# IOBRMEGA.net
KiCad netlist of a schematic drawn in EAGLE
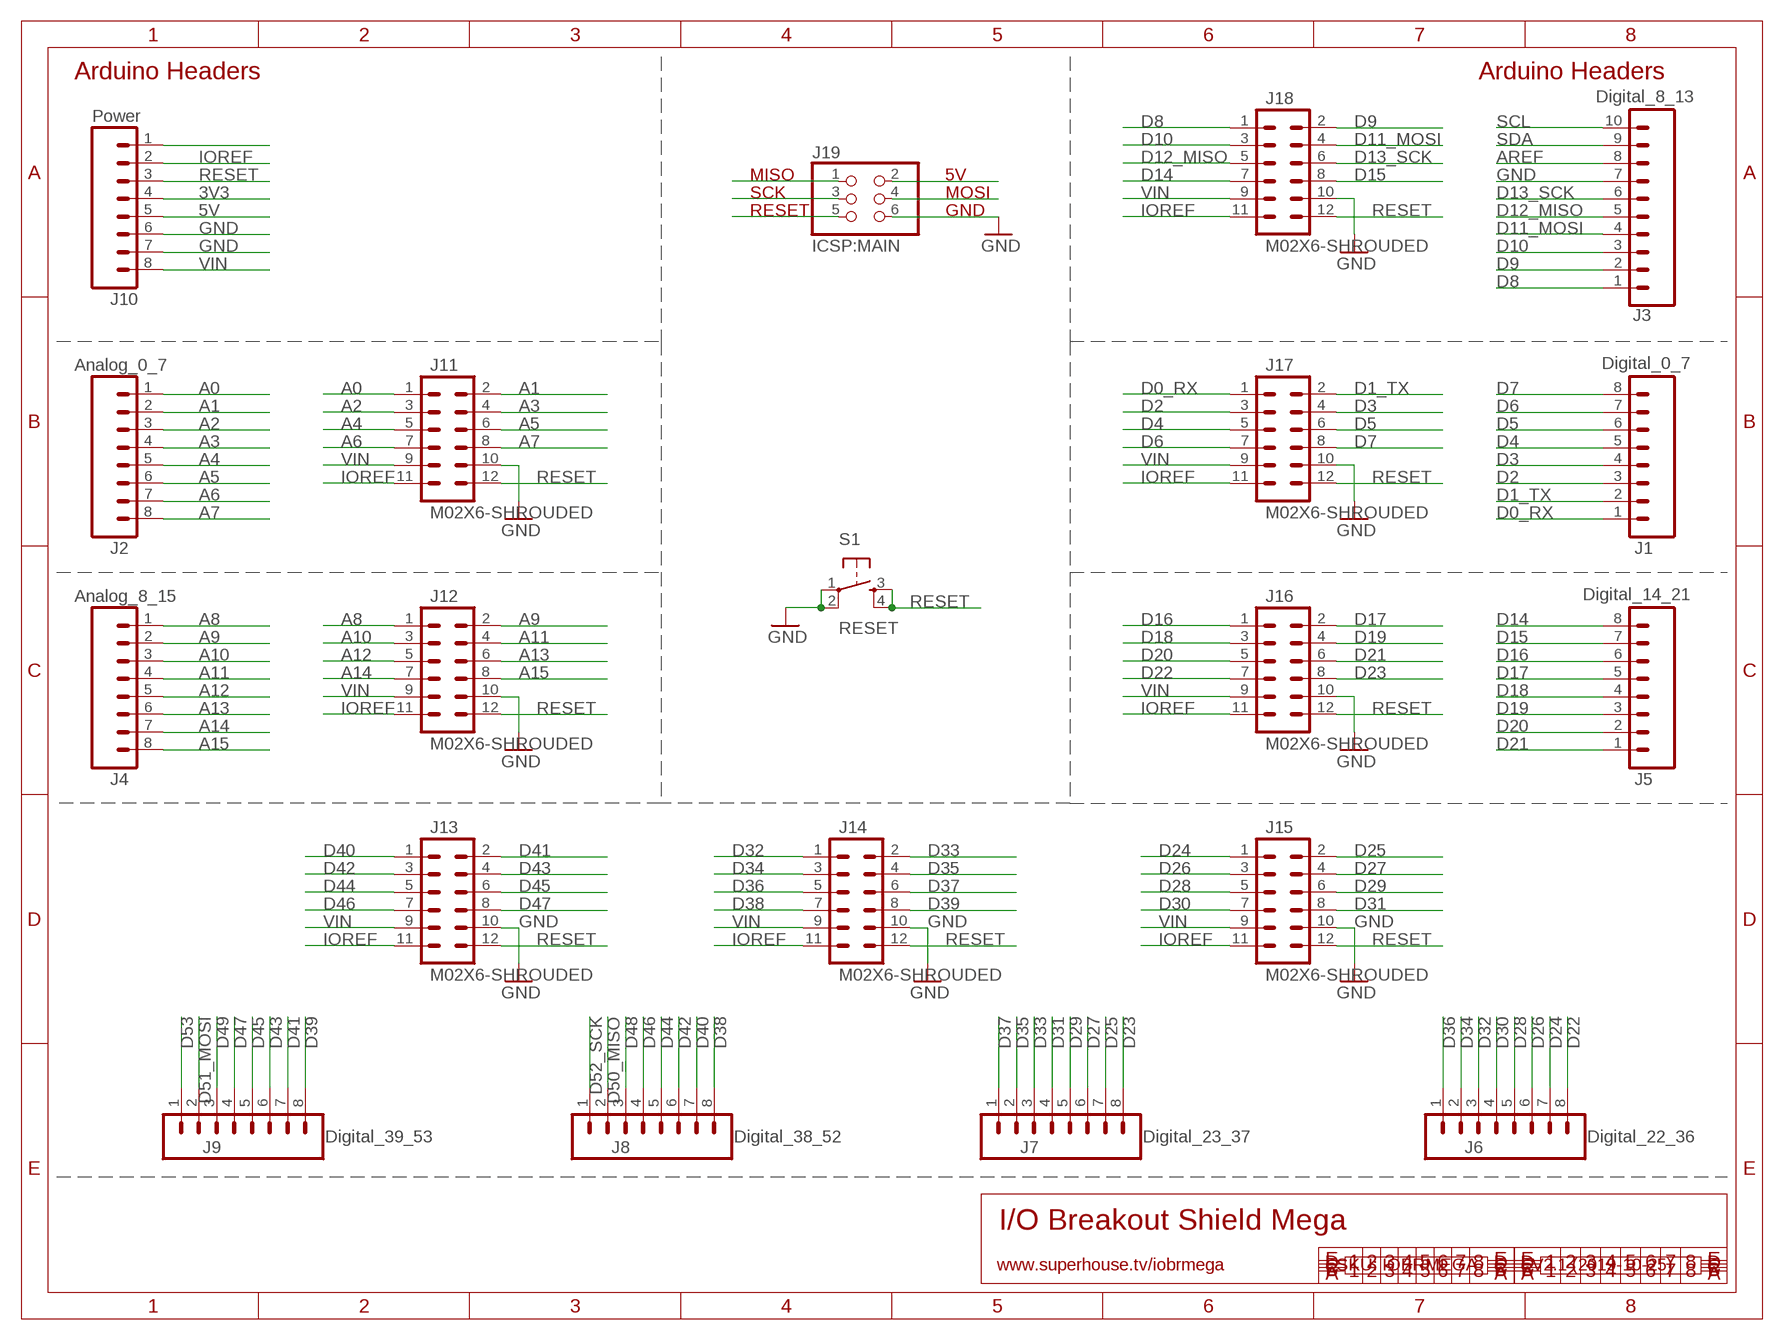
[diagram p0: schematic, sheet 1]

(export (version "E")
  (design (tool "Eeschema 10.0.6"))
  (components
    (comp (ref "J1")
      (value "Digital_0_7")
      (footprint "eagle-import:1X08-P-BELOW")
      (libsource (lib "eagle-import") (part "M08-PIN-BELOW"))
    )
    (comp (ref "J2")
      (value "Analog_0_7")
      (footprint "eagle-import:1X08-P-BELOW")
      (libsource (lib "eagle-import") (part "M08-PIN-BELOW"))
    )
    (comp (ref "J3")
      (value "Digital_8_13")
      (footprint "eagle-import:1X10-P-BELOW")
      (libsource (lib "eagle-import") (part "M10-PIN-BELOW"))
    )
    (comp (ref "J4")
      (value "Analog_8_15")
      (footprint "eagle-import:1X08-P-BELOW")
      (libsource (lib "eagle-import") (part "M08-PIN-BELOW"))
    )
    (comp (ref "J5")
      (value "Digital_14_21")
      (footprint "eagle-import:1X08-P-BELOW")
      (libsource (lib "eagle-import") (part "M08-PIN-BELOW"))
    )
    (comp (ref "J6")
      (value "Digital_22_36")
      (footprint "eagle-import:1X08-P-BELOW")
      (libsource (lib "eagle-import") (part "M08-PIN-BELOW"))
    )
    (comp (ref "J7")
      (value "Digital_23_37")
      (footprint "eagle-import:1X08-P-BELOW")
      (libsource (lib "eagle-import") (part "M08-PIN-BELOW"))
    )
    (comp (ref "J8")
      (value "Digital_38_52")
      (footprint "eagle-import:1X08-P-BELOW")
      (libsource (lib "eagle-import") (part "M08-PIN-BELOW"))
    )
    (comp (ref "J9")
      (value "Digital_39_53")
      (footprint "eagle-import:1X08-P-BELOW")
      (libsource (lib "eagle-import") (part "M08-PIN-BELOW"))
    )
    (comp (ref "J10")
      (value "Power")
      (footprint "eagle-import:1X08-P-BELOW")
      (libsource (lib "eagle-import") (part "M08-PIN-BELOW"))
    )
    (comp (ref "J11")
      (value "M02X6-SHROUDED")
      (footprint "eagle-import:2X06-SHROUDED")
      (libsource (lib "eagle-import") (part "M02X6-SHROUDED"))
    )
    (comp (ref "J12")
      (value "M02X6-SHROUDED")
      (footprint "eagle-import:2X06-SHROUDED")
      (libsource (lib "eagle-import") (part "M02X6-SHROUDED"))
    )
    (comp (ref "J13")
      (value "M02X6-SHROUDED")
      (footprint "eagle-import:2X06-SHROUDED")
      (libsource (lib "eagle-import") (part "M02X6-SHROUDED"))
    )
    (comp (ref "J14")
      (value "M02X6-SHROUDED")
      (footprint "eagle-import:2X06-SHROUDED")
      (libsource (lib "eagle-import") (part "M02X6-SHROUDED"))
    )
    (comp (ref "J15")
      (value "M02X6-SHROUDED")
      (footprint "eagle-import:2X06-SHROUDED")
      (libsource (lib "eagle-import") (part "M02X6-SHROUDED"))
    )
    (comp (ref "J16")
      (value "M02X6-SHROUDED")
      (footprint "eagle-import:2X06-SHROUDED")
      (libsource (lib "eagle-import") (part "M02X6-SHROUDED"))
    )
    (comp (ref "J17")
      (value "M02X6-SHROUDED")
      (footprint "eagle-import:2X06-SHROUDED")
      (libsource (lib "eagle-import") (part "M02X6-SHROUDED"))
    )
    (comp (ref "J18")
      (value "M02X6-SHROUDED")
      (footprint "eagle-import:2X06-SHROUDED")
      (libsource (lib "eagle-import") (part "M02X6-SHROUDED"))
    )
    (comp (ref "J19")
      (value "ICSP:MAIN")
      (footprint "eagle-import:2X03")
      (libsource (lib "eagle-import") (part "PINHD-2X3"))
    )
    (comp (ref "S1")
      (value "RESET")
      (footprint "eagle-import:TACTILE-PTH-6MM")
      (libsource (lib "eagle-import") (part "TAC_SWITCH-PTH-6"))
    )
  )
  (nets
    (net (code "1") (name "/3V3") (class "Default")
      (node (ref "J10") (pin "4") (pinfunction "4_4") (pintype "passive"))
    )
    (net (code "2") (name "/5V") (class "Default")
      (node (ref "J10") (pin "5") (pinfunction "5_5") (pintype "passive"))
    )
    (net (code "3") (name "/A0") (class "Default")
      (node (ref "J11") (pin "1") (pinfunction "1_1") (pintype "passive"))
      (node (ref "J2") (pin "1") (pinfunction "1_1") (pintype "passive"))
    )
    (net (code "4") (name "/A1") (class "Default")
      (node (ref "J11") (pin "2") (pinfunction "2_2") (pintype "passive"))
      (node (ref "J2") (pin "2") (pinfunction "2_2") (pintype "passive"))
    )
    (net (code "5") (name "/A2") (class "Default")
      (node (ref "J11") (pin "3") (pinfunction "3_3") (pintype "passive"))
      (node (ref "J2") (pin "3") (pinfunction "3_3") (pintype "passive"))
    )
    (net (code "6") (name "/A3") (class "Default")
      (node (ref "J11") (pin "4") (pinfunction "4_4") (pintype "passive"))
      (node (ref "J2") (pin "4") (pinfunction "4_4") (pintype "passive"))
    )
    (net (code "7") (name "/A4") (class "Default")
      (node (ref "J11") (pin "5") (pinfunction "5_5") (pintype "passive"))
      (node (ref "J2") (pin "5") (pinfunction "5_5") (pintype "passive"))
    )
    (net (code "8") (name "/A5") (class "Default")
      (node (ref "J11") (pin "6") (pinfunction "6_6") (pintype "passive"))
      (node (ref "J2") (pin "6") (pinfunction "6_6") (pintype "passive"))
    )
    (net (code "9") (name "/A6") (class "Default")
      (node (ref "J11") (pin "7") (pinfunction "7_7") (pintype "passive"))
      (node (ref "J2") (pin "7") (pinfunction "7_7") (pintype "passive"))
    )
    (net (code "10") (name "/A7") (class "Default")
      (node (ref "J11") (pin "8") (pinfunction "8_8") (pintype "passive"))
      (node (ref "J2") (pin "8") (pinfunction "8_8") (pintype "passive"))
    )
    (net (code "11") (name "/A8") (class "Default")
      (node (ref "J12") (pin "1") (pinfunction "1_1") (pintype "passive"))
      (node (ref "J4") (pin "1") (pinfunction "1_1") (pintype "passive"))
    )
    (net (code "12") (name "/A9") (class "Default")
      (node (ref "J12") (pin "2") (pinfunction "2_2") (pintype "passive"))
      (node (ref "J4") (pin "2") (pinfunction "2_2") (pintype "passive"))
    )
    (net (code "13") (name "/A10") (class "Default")
      (node (ref "J12") (pin "3") (pinfunction "3_3") (pintype "passive"))
      (node (ref "J4") (pin "3") (pinfunction "3_3") (pintype "passive"))
    )
    (net (code "14") (name "/A11") (class "Default")
      (node (ref "J12") (pin "4") (pinfunction "4_4") (pintype "passive"))
      (node (ref "J4") (pin "4") (pinfunction "4_4") (pintype "passive"))
    )
    (net (code "15") (name "/A12") (class "Default")
      (node (ref "J12") (pin "5") (pinfunction "5_5") (pintype "passive"))
      (node (ref "J4") (pin "5") (pinfunction "5_5") (pintype "passive"))
    )
    (net (code "16") (name "/A13") (class "Default")
      (node (ref "J12") (pin "6") (pinfunction "6_6") (pintype "passive"))
      (node (ref "J4") (pin "6") (pinfunction "6_6") (pintype "passive"))
    )
    (net (code "17") (name "/A14") (class "Default")
      (node (ref "J12") (pin "7") (pinfunction "7_7") (pintype "passive"))
      (node (ref "J4") (pin "7") (pinfunction "7_7") (pintype "passive"))
    )
    (net (code "18") (name "/A15") (class "Default")
      (node (ref "J12") (pin "8") (pinfunction "8_8") (pintype "passive"))
      (node (ref "J4") (pin "8") (pinfunction "8_8") (pintype "passive"))
    )
    (net (code "19") (name "/AREF") (class "Default")
      (node (ref "J3") (pin "8") (pinfunction "8_8") (pintype "passive"))
    )
    (net (code "20") (name "/D0_RX") (class "Default")
      (node (ref "J1") (pin "1") (pinfunction "1_1") (pintype "passive"))
      (node (ref "J17") (pin "1") (pinfunction "1_1") (pintype "passive"))
    )
    (net (code "21") (name "/D1_TX") (class "Default")
      (node (ref "J1") (pin "2") (pinfunction "2_2") (pintype "passive"))
      (node (ref "J17") (pin "2") (pinfunction "2_2") (pintype "passive"))
    )
    (net (code "22") (name "/D2") (class "Default")
      (node (ref "J1") (pin "3") (pinfunction "3_3") (pintype "passive"))
      (node (ref "J17") (pin "3") (pinfunction "3_3") (pintype "passive"))
    )
    (net (code "23") (name "/D3") (class "Default")
      (node (ref "J1") (pin "4") (pinfunction "4_4") (pintype "passive"))
      (node (ref "J17") (pin "4") (pinfunction "4_4") (pintype "passive"))
    )
    (net (code "24") (name "/D4") (class "Default")
      (node (ref "J1") (pin "5") (pinfunction "5_5") (pintype "passive"))
      (node (ref "J17") (pin "5") (pinfunction "5_5") (pintype "passive"))
    )
    (net (code "25") (name "/D5") (class "Default")
      (node (ref "J1") (pin "6") (pinfunction "6_6") (pintype "passive"))
      (node (ref "J17") (pin "6") (pinfunction "6_6") (pintype "passive"))
    )
    (net (code "26") (name "/D6") (class "Default")
      (node (ref "J1") (pin "7") (pinfunction "7_7") (pintype "passive"))
      (node (ref "J17") (pin "7") (pinfunction "7_7") (pintype "passive"))
    )
    (net (code "27") (name "/D7") (class "Default")
      (node (ref "J1") (pin "8") (pinfunction "8_8") (pintype "passive"))
      (node (ref "J17") (pin "8") (pinfunction "8_8") (pintype "passive"))
    )
    (net (code "28") (name "/D8") (class "Default")
      (node (ref "J18") (pin "1") (pinfunction "1_1") (pintype "passive"))
      (node (ref "J3") (pin "1") (pinfunction "1_1") (pintype "passive"))
    )
    (net (code "29") (name "/D9") (class "Default")
      (node (ref "J18") (pin "2") (pinfunction "2_2") (pintype "passive"))
      (node (ref "J3") (pin "2") (pinfunction "2_2") (pintype "passive"))
    )
    (net (code "30") (name "/D10") (class "Default")
      (node (ref "J18") (pin "3") (pinfunction "3_3") (pintype "passive"))
      (node (ref "J3") (pin "3") (pinfunction "3_3") (pintype "passive"))
    )
    (net (code "31") (name "/D11_MOSI") (class "Default")
      (node (ref "J18") (pin "4") (pinfunction "4_4") (pintype "passive"))
      (node (ref "J3") (pin "4") (pinfunction "4_4") (pintype "passive"))
    )
    (net (code "32") (name "/D12_MISO") (class "Default")
      (node (ref "J18") (pin "5") (pinfunction "5_5") (pintype "passive"))
      (node (ref "J3") (pin "5") (pinfunction "5_5") (pintype "passive"))
    )
    (net (code "33") (name "/D13_SCK") (class "Default")
      (node (ref "J18") (pin "6") (pinfunction "6_6") (pintype "passive"))
      (node (ref "J3") (pin "6") (pinfunction "6_6") (pintype "passive"))
    )
    (net (code "34") (name "/D14") (class "Default")
      (node (ref "J18") (pin "7") (pinfunction "7_7") (pintype "passive"))
      (node (ref "J5") (pin "8") (pinfunction "8_8") (pintype "passive"))
    )
    (net (code "35") (name "/D15") (class "Default")
      (node (ref "J18") (pin "8") (pinfunction "8_8") (pintype "passive"))
      (node (ref "J5") (pin "7") (pinfunction "7_7") (pintype "passive"))
    )
    (net (code "36") (name "/D16") (class "Default")
      (node (ref "J16") (pin "1") (pinfunction "1_1") (pintype "passive"))
      (node (ref "J5") (pin "6") (pinfunction "6_6") (pintype "passive"))
    )
    (net (code "37") (name "/D17") (class "Default")
      (node (ref "J16") (pin "2") (pinfunction "2_2") (pintype "passive"))
      (node (ref "J5") (pin "5") (pinfunction "5_5") (pintype "passive"))
    )
    (net (code "38") (name "/D18") (class "Default")
      (node (ref "J16") (pin "3") (pinfunction "3_3") (pintype "passive"))
      (node (ref "J5") (pin "4") (pinfunction "4_4") (pintype "passive"))
    )
    (net (code "39") (name "/D19") (class "Default")
      (node (ref "J16") (pin "4") (pinfunction "4_4") (pintype "passive"))
      (node (ref "J5") (pin "3") (pinfunction "3_3") (pintype "passive"))
    )
    (net (code "40") (name "/D20") (class "Default")
      (node (ref "J16") (pin "5") (pinfunction "5_5") (pintype "passive"))
      (node (ref "J5") (pin "2") (pinfunction "2_2") (pintype "passive"))
    )
    (net (code "41") (name "/D21") (class "Default")
      (node (ref "J16") (pin "6") (pinfunction "6_6") (pintype "passive"))
      (node (ref "J5") (pin "1") (pinfunction "1_1") (pintype "passive"))
    )
    (net (code "42") (name "/D22") (class "Default")
      (node (ref "J16") (pin "7") (pinfunction "7_7") (pintype "passive"))
      (node (ref "J6") (pin "8") (pinfunction "8_8") (pintype "passive"))
    )
    (net (code "43") (name "/D23") (class "Default")
      (node (ref "J16") (pin "8") (pinfunction "8_8") (pintype "passive"))
      (node (ref "J7") (pin "8") (pinfunction "8_8") (pintype "passive"))
    )
    (net (code "44") (name "/D24") (class "Default")
      (node (ref "J15") (pin "1") (pinfunction "1_1") (pintype "passive"))
      (node (ref "J6") (pin "7") (pinfunction "7_7") (pintype "passive"))
    )
    (net (code "45") (name "/D25") (class "Default")
      (node (ref "J15") (pin "2") (pinfunction "2_2") (pintype "passive"))
      (node (ref "J7") (pin "7") (pinfunction "7_7") (pintype "passive"))
    )
    (net (code "46") (name "/D26") (class "Default")
      (node (ref "J15") (pin "3") (pinfunction "3_3") (pintype "passive"))
      (node (ref "J6") (pin "6") (pinfunction "6_6") (pintype "passive"))
    )
    (net (code "47") (name "/D27") (class "Default")
      (node (ref "J15") (pin "4") (pinfunction "4_4") (pintype "passive"))
      (node (ref "J7") (pin "6") (pinfunction "6_6") (pintype "passive"))
    )
    (net (code "48") (name "/D28") (class "Default")
      (node (ref "J15") (pin "5") (pinfunction "5_5") (pintype "passive"))
      (node (ref "J6") (pin "5") (pinfunction "5_5") (pintype "passive"))
    )
    (net (code "49") (name "/D29") (class "Default")
      (node (ref "J15") (pin "6") (pinfunction "6_6") (pintype "passive"))
      (node (ref "J7") (pin "5") (pinfunction "5_5") (pintype "passive"))
    )
    (net (code "50") (name "/D30") (class "Default")
      (node (ref "J15") (pin "7") (pinfunction "7_7") (pintype "passive"))
      (node (ref "J6") (pin "4") (pinfunction "4_4") (pintype "passive"))
    )
    (net (code "51") (name "/D31") (class "Default")
      (node (ref "J15") (pin "8") (pinfunction "8_8") (pintype "passive"))
      (node (ref "J7") (pin "4") (pinfunction "4_4") (pintype "passive"))
    )
    (net (code "52") (name "/D32") (class "Default")
      (node (ref "J14") (pin "1") (pinfunction "1_1") (pintype "passive"))
      (node (ref "J6") (pin "3") (pinfunction "3_3") (pintype "passive"))
    )
    (net (code "53") (name "/D33") (class "Default")
      (node (ref "J14") (pin "2") (pinfunction "2_2") (pintype "passive"))
      (node (ref "J7") (pin "3") (pinfunction "3_3") (pintype "passive"))
    )
    (net (code "54") (name "/D34") (class "Default")
      (node (ref "J14") (pin "3") (pinfunction "3_3") (pintype "passive"))
      (node (ref "J6") (pin "2") (pinfunction "2_2") (pintype "passive"))
    )
    (net (code "55") (name "/D35") (class "Default")
      (node (ref "J14") (pin "4") (pinfunction "4_4") (pintype "passive"))
      (node (ref "J7") (pin "2") (pinfunction "2_2") (pintype "passive"))
    )
    (net (code "56") (name "/D36") (class "Default")
      (node (ref "J14") (pin "5") (pinfunction "5_5") (pintype "passive"))
      (node (ref "J6") (pin "1") (pinfunction "1_1") (pintype "passive"))
    )
    (net (code "57") (name "/D37") (class "Default")
      (node (ref "J14") (pin "6") (pinfunction "6_6") (pintype "passive"))
      (node (ref "J7") (pin "1") (pinfunction "1_1") (pintype "passive"))
    )
    (net (code "58") (name "/D38") (class "Default")
      (node (ref "J14") (pin "7") (pinfunction "7_7") (pintype "passive"))
      (node (ref "J8") (pin "8") (pinfunction "8_8") (pintype "passive"))
    )
    (net (code "59") (name "/D39") (class "Default")
      (node (ref "J14") (pin "8") (pinfunction "8_8") (pintype "passive"))
      (node (ref "J9") (pin "8") (pinfunction "8_8") (pintype "passive"))
    )
    (net (code "60") (name "/D40") (class "Default")
      (node (ref "J13") (pin "1") (pinfunction "1_1") (pintype "passive"))
      (node (ref "J8") (pin "7") (pinfunction "7_7") (pintype "passive"))
    )
    (net (code "61") (name "/D41") (class "Default")
      (node (ref "J13") (pin "2") (pinfunction "2_2") (pintype "passive"))
      (node (ref "J9") (pin "7") (pinfunction "7_7") (pintype "passive"))
    )
    (net (code "62") (name "/D42") (class "Default")
      (node (ref "J13") (pin "3") (pinfunction "3_3") (pintype "passive"))
      (node (ref "J8") (pin "6") (pinfunction "6_6") (pintype "passive"))
    )
    (net (code "63") (name "/D43") (class "Default")
      (node (ref "J13") (pin "4") (pinfunction "4_4") (pintype "passive"))
      (node (ref "J9") (pin "6") (pinfunction "6_6") (pintype "passive"))
    )
    (net (code "64") (name "/D44") (class "Default")
      (node (ref "J13") (pin "5") (pinfunction "5_5") (pintype "passive"))
      (node (ref "J8") (pin "5") (pinfunction "5_5") (pintype "passive"))
    )
    (net (code "65") (name "/D45") (class "Default")
      (node (ref "J13") (pin "6") (pinfunction "6_6") (pintype "passive"))
      (node (ref "J9") (pin "5") (pinfunction "5_5") (pintype "passive"))
    )
    (net (code "66") (name "/D46") (class "Default")
      (node (ref "J13") (pin "7") (pinfunction "7_7") (pintype "passive"))
      (node (ref "J8") (pin "4") (pinfunction "4_4") (pintype "passive"))
    )
    (net (code "67") (name "/D47") (class "Default")
      (node (ref "J13") (pin "8") (pinfunction "8_8") (pintype "passive"))
      (node (ref "J9") (pin "4") (pinfunction "4_4") (pintype "passive"))
    )
    (net (code "68") (name "/D48") (class "Default")
      (node (ref "J8") (pin "3") (pinfunction "3_3") (pintype "passive"))
    )
    (net (code "69") (name "/D49") (class "Default")
      (node (ref "J9") (pin "3") (pinfunction "3_3") (pintype "passive"))
    )
    (net (code "70") (name "/D50_MISO") (class "Default")
      (node (ref "J8") (pin "2") (pinfunction "2_2") (pintype "passive"))
    )
    (net (code "71") (name "/D51_MOSI") (class "Default")
      (node (ref "J9") (pin "2") (pinfunction "2_2") (pintype "passive"))
    )
    (net (code "72") (name "/D52_SCK") (class "Default")
      (node (ref "J8") (pin "1") (pinfunction "1_1") (pintype "passive"))
    )
    (net (code "73") (name "/D53") (class "Default")
      (node (ref "J9") (pin "1") (pinfunction "1_1") (pintype "passive"))
    )
    (net (code "74") (name "/IOREF") (class "Default")
      (node (ref "J10") (pin "2") (pinfunction "2_2") (pintype "passive"))
      (node (ref "J11") (pin "11") (pinfunction "11_11") (pintype "passive"))
      (node (ref "J12") (pin "11") (pinfunction "11_11") (pintype "passive"))
      (node (ref "J13") (pin "11") (pinfunction "11_11") (pintype "passive"))
      (node (ref "J14") (pin "11") (pinfunction "11_11") (pintype "passive"))
      (node (ref "J15") (pin "11") (pinfunction "11_11") (pintype "passive"))
      (node (ref "J16") (pin "11") (pinfunction "11_11") (pintype "passive"))
      (node (ref "J17") (pin "11") (pinfunction "11_11") (pintype "passive"))
      (node (ref "J18") (pin "11") (pinfunction "11_11") (pintype "passive"))
    )
    (net (code "75") (name "/RESET") (class "Default")
      (node (ref "J10") (pin "3") (pinfunction "3_3") (pintype "passive"))
      (node (ref "J11") (pin "12") (pinfunction "12_12") (pintype "passive"))
      (node (ref "J12") (pin "12") (pinfunction "12_12") (pintype "passive"))
      (node (ref "J13") (pin "12") (pinfunction "12_12") (pintype "passive"))
      (node (ref "J14") (pin "12") (pinfunction "12_12") (pintype "passive"))
      (node (ref "J15") (pin "12") (pinfunction "12_12") (pintype "passive"))
      (node (ref "J16") (pin "12") (pinfunction "12_12") (pintype "passive"))
      (node (ref "J17") (pin "12") (pinfunction "12_12") (pintype "passive"))
      (node (ref "J18") (pin "12") (pinfunction "12_12") (pintype "passive"))
      (node (ref "S1") (pin "3") (pinfunction "3_3") (pintype "passive"))
      (node (ref "S1") (pin "4") (pinfunction "4_4") (pintype "passive"))
    )
    (net (code "76") (name "/SCL") (class "Default")
      (node (ref "J3") (pin "10") (pinfunction "10_10") (pintype "passive"))
    )
    (net (code "77") (name "/SDA") (class "Default")
      (node (ref "J3") (pin "9") (pinfunction "9_9") (pintype "passive"))
    )
    (net (code "78") (name "/VIN") (class "Default")
      (node (ref "J10") (pin "8") (pinfunction "8_8") (pintype "passive"))
      (node (ref "J11") (pin "9") (pinfunction "9_9") (pintype "passive"))
      (node (ref "J12") (pin "9") (pinfunction "9_9") (pintype "passive"))
      (node (ref "J13") (pin "9") (pinfunction "9_9") (pintype "passive"))
      (node (ref "J14") (pin "9") (pinfunction "9_9") (pintype "passive"))
      (node (ref "J15") (pin "9") (pinfunction "9_9") (pintype "passive"))
      (node (ref "J16") (pin "9") (pinfunction "9_9") (pintype "passive"))
      (node (ref "J17") (pin "9") (pinfunction "9_9") (pintype "passive"))
      (node (ref "J18") (pin "9") (pinfunction "9_9") (pintype "passive"))
    )
    (net (code "79") (name "GND") (class "Default")
      (node (ref "J10") (pin "6") (pinfunction "6_6") (pintype "passive"))
      (node (ref "J10") (pin "7") (pinfunction "7_7") (pintype "passive"))
      (node (ref "J11") (pin "10") (pinfunction "10_10") (pintype "passive"))
      (node (ref "J12") (pin "10") (pinfunction "10_10") (pintype "passive"))
      (node (ref "J13") (pin "10") (pinfunction "10_10") (pintype "passive"))
      (node (ref "J14") (pin "10") (pinfunction "10_10") (pintype "passive"))
      (node (ref "J15") (pin "10") (pinfunction "10_10") (pintype "passive"))
      (node (ref "J16") (pin "10") (pinfunction "10_10") (pintype "passive"))
      (node (ref "J17") (pin "10") (pinfunction "10_10") (pintype "passive"))
      (node (ref "J18") (pin "10") (pinfunction "10_10") (pintype "passive"))
      (node (ref "J19") (pin "6") (pinfunction "6_6") (pintype "passive"))
      (node (ref "J3") (pin "7") (pinfunction "7_7") (pintype "passive"))
      (node (ref "S1") (pin "1") (pinfunction "1_1") (pintype "passive"))
      (node (ref "S1") (pin "2") (pinfunction "2_2") (pintype "passive"))
    )
    (net (code "80") (name "unconnected-(J10-Pad1)") (class "Default")
      (node (ref "J10") (pin "1") (pinfunction "1_1") (pintype "passive"))
    )
    (net (code "81") (name "unconnected-(J19-Pad1)") (class "Default")
      (node (ref "J19") (pin "1") (pinfunction "1_1") (pintype "passive"))
    )
    (net (code "82") (name "unconnected-(J19-Pad2)") (class "Default")
      (node (ref "J19") (pin "2") (pinfunction "2_2") (pintype "passive"))
    )
    (net (code "83") (name "unconnected-(J19-Pad3)") (class "Default")
      (node (ref "J19") (pin "3") (pinfunction "3_3") (pintype "passive"))
    )
    (net (code "84") (name "unconnected-(J19-Pad4)") (class "Default")
      (node (ref "J19") (pin "4") (pinfunction "4_4") (pintype "passive"))
    )
    (net (code "85") (name "unconnected-(J19-Pad5)") (class "Default")
      (node (ref "J19") (pin "5") (pinfunction "5_5") (pintype "passive"))
    )
  )
)
